# 02_SRAD_Avionics.net
KiCad netlist of a schematic drawn in Altium Designer
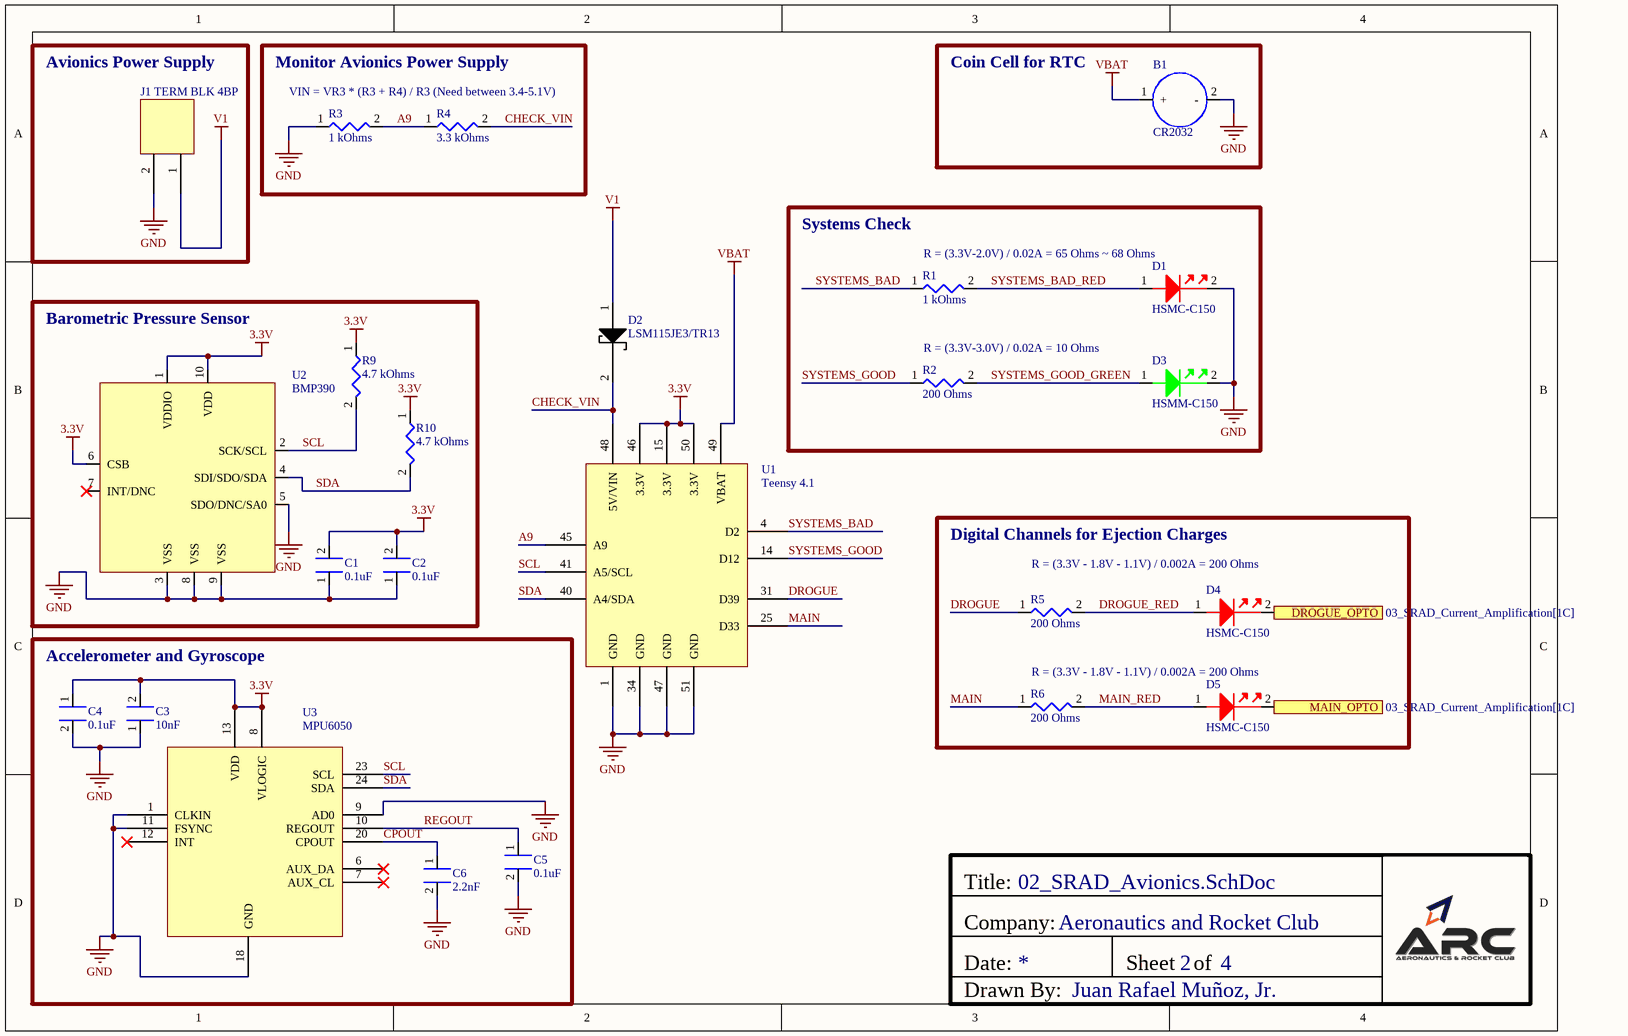
[diagram p0: 02_SRAD_Avionics.SchDoc]

(export (version "E")
  (design (tool "Eeschema 10.0.6"))
  (components
    (comp (ref "B1")
      (value "CR2032")
      (footprint "CR2032")
      (description "CR2032 Coin cell battery of 3V.")
      (libsource (lib "SRAD_SAC_Schlib") (part "CR2032"))
    )
    (comp (ref "C1")
      (value "0.1uF")
      (footprint "CAPC2012X14N_1_35mm_HEIGHT")
      (description "Capacitor Multilayer Ceramic MLCC - SMD/SMT 25 V 0.1uF X7R 0805 5%")
      (fields
        (field (name "MANUFACTURER") "Yageo")
        (field (name "MANUFACTURER PART NUMBER") "CC0805JPX7R8BB104")
      )
      (libsource (lib "SRAD_SAC_Schlib") (part "CC0805JPX7R8BB104"))
    )
    (comp (ref "C2")
      (value "0.1uF")
      (footprint "CAPC2012X14N_1_35mm_HEIGHT")
      (description "Capacitor Multilayer Ceramic MLCC - SMD/SMT 25 V 0.1uF X7R 0805 5%")
      (fields
        (field (name "MANUFACTURER") "Yageo")
        (field (name "MANUFACTURER PART NUMBER") "CC0805JPX7R8BB104")
      )
      (libsource (lib "SRAD_SAC_Schlib") (part "CC0805JPX7R8BB104"))
    )
    (comp (ref "C3")
      (value "10nF")
      (footprint "CAPC2012X07N_06mmHEIGHT")
      (description "Capacitor Multilayer Ceramic MLCC - SMD/SMT 50V 10nF X7R 0805 5%")
      (fields
        (field (name "MANUFACTURER") "Yageo")
        (field (name "MANUFACTURER PART NUMBER") "CC0805JRX7R9BB103")
      )
      (libsource (lib "SRAD_SAC_Schlib") (part "CC0805JRX7R9BB103"))
    )
    (comp (ref "C4")
      (value "0.1uF")
      (footprint "CAPC2012X14N_1_35mm_HEIGHT")
      (description "Capacitor Multilayer Ceramic MLCC - SMD/SMT 25 V 0.1uF X7R 0805 5%")
      (fields
        (field (name "MANUFACTURER") "Yageo")
        (field (name "MANUFACTURER PART NUMBER") "CC0805JPX7R8BB104")
      )
      (libsource (lib "SRAD_SAC_Schlib") (part "CC0805JPX7R8BB104"))
    )
    (comp (ref "C5")
      (value "0.1uF")
      (footprint "CAPC2012X14N_1_35mm_HEIGHT")
      (description "Capacitor Multilayer Ceramic MLCC - SMD/SMT 25 V 0.1uF X7R 0805 5%")
      (fields
        (field (name "MANUFACTURER") "Yageo")
        (field (name "MANUFACTURER PART NUMBER") "CC0805JPX7R8BB104")
      )
      (libsource (lib "SRAD_SAC_Schlib") (part "CC0805JPX7R8BB104"))
    )
    (comp (ref "C6")
      (value "2.2nF")
      (footprint "CAPC2012X07N_06mmHEIGHT")
      (description "Capacitor Multilayer Ceramic MLCC - SMD/SMT 50 V 2.2nF X7R 0805 5%")
      (fields
        (field (name "MANUFACTURER") "Yageo")
        (field (name "MANUFACTURER PART NUMBER") "CC0805JRX7R9BB222")
      )
      (libsource (lib "SRAD_SAC_Schlib") (part "CC0805JRX7R9BB222"))
    )
    (comp (ref "D1")
      (value "HSMC-C150")
      (footprint "DIOM3216X12N RED")
      (description "Red 626nm LED Indication - Discrete 1.9V 1206 (3216 Metric)")
      (fields (field (name "MANUFACTURER") "Broadcom Avago"))
      (libsource (lib "SRAD_SAC_Schlib") (part "DIOM3216X12N RED"))
    )
    (comp (ref "D2")
      (value "LSM115JE3/TR13")
      (footprint "DIOM4336X33N")
      (fields (field (name "MANUFACTURER") "Microchip"))
      (libsource (lib "SRAD_SAC_Schlib") (part "DIOM4336X33N Schottky Diode"))
    )
    (comp (ref "D3")
      (value "HSMM-C150")
      (footprint "DIOM3216X12N GREEN")
      (description "Green 525nm LED Indication - Discrete 3.3V 1206 (3216 Metric)")
      (fields (field (name "MANUFACTURER") "Broadcom Avago"))
      (libsource (lib "SRAD_SAC_Schlib") (part "DIOM3216X12N GREEN"))
    )
    (comp (ref "D4")
      (value "HSMC-C150")
      (footprint "DIOM3216X12N RED")
      (description "Red 626nm LED Indication - Discrete 1.9V 1206 (3216 Metric)")
      (fields (field (name "MANUFACTURER") "Broadcom Avago"))
      (libsource (lib "SRAD_SAC_Schlib") (part "DIOM3216X12N RED"))
    )
    (comp (ref "D5")
      (value "HSMC-C150")
      (footprint "DIOM3216X12N RED")
      (description "Red 626nm LED Indication - Discrete 1.9V 1206 (3216 Metric)")
      (fields (field (name "MANUFACTURER") "Broadcom Avago"))
      (libsource (lib "SRAD_SAC_Schlib") (part "DIOM3216X12N RED"))
    )
    (comp (ref "J1")
      (value "TERM BLK 4BP")
      (footprint "PCB TERM BLK 2P 2.54MM")
      (fields
        (field (name "MANUFACTURER") "TE Connectivity")
        (field (name "MANUFACTURER PART NUMBER") "282834-2")
        (field (name "VOLTAGE") "150V")
      )
      (libsource (lib "SRAD_SAC_Schlib") (part "PCB TERM BLK 2P 2.54MM"))
    )
    (comp (ref "R1")
      (value "1 kOhms")
      (footprint "RESC2012X06N")
      (description "1 kOhms ±1% 0.25W, 1/4W Chip Resistor 0805 (2012 Metric) Moisture Resistant Thick Film")
      (fields
        (field (name "MANUFACTURER") "Yageo")
        (field (name "MANUFACTURER PART NUMBER") "RC0805FR-7W1KL")
      )
      (libsource (lib "SRAD_SAC_Schlib") (part "RC0805FR-7W1KL Yageo"))
    )
    (comp (ref "R2")
      (value "200 Ohms")
      (footprint "RESC2012X06N")
      (description "200 Ohms ±1% 0.25W, 1/4W Chip Resistor 0805 (2012 Metric) Moisture Resistant Thick Film")
      (fields
        (field (name "MANUFACTURER") "Yageo")
        (field (name "MANUFACTURER PART NUMBER") "RC0805FR-7W200RL")
      )
      (libsource (lib "SRAD_SAC_Schlib") (part "RC0805FR-7W200RL Yageo"))
    )
    (comp (ref "R3")
      (value "1 kOhms")
      (footprint "RESC2012X06N")
      (description "1 kOhms ±1% 0.25W, 1/4W Chip Resistor 0805 (2012 Metric) Moisture Resistant Thick Film")
      (fields
        (field (name "MANUFACTURER") "Yageo")
        (field (name "MANUFACTURER PART NUMBER") "RC0805FR-7W1KL")
      )
      (libsource (lib "SRAD_SAC_Schlib") (part "RC0805FR-7W1KL Yageo"))
    )
    (comp (ref "R4")
      (value "3.3 kOhms")
      (footprint "RESC2012X06N")
      (description "3.3 kOhms ±1% 0.25W, 1/4W Chip Resistor 0805 (2012 Metric) Moisture Resistant Thick Film")
      (fields
        (field (name "MANUFACTURER") "Yageo")
        (field (name "MANUFACTURER PART NUMBER") "RC0805FR-7W3K3L")
      )
      (libsource (lib "SRAD_SAC_Schlib") (part "RC0805FR-7W3K3L Yageo"))
    )
    (comp (ref "R5")
      (value "200 Ohms")
      (footprint "RESC2012X06N")
      (description "200 Ohms ±1% 0.25W, 1/4W Chip Resistor 0805 (2012 Metric) Moisture Resistant Thick Film")
      (fields
        (field (name "MANUFACTURER") "Yageo")
        (field (name "MANUFACTURER PART NUMBER") "RC0805FR-7W200RL")
      )
      (libsource (lib "SRAD_SAC_Schlib") (part "RC0805FR-7W200RL Yageo"))
    )
    (comp (ref "R6")
      (value "200 Ohms")
      (footprint "RESC2012X06N")
      (description "200 Ohms ±1% 0.25W, 1/4W Chip Resistor 0805 (2012 Metric) Moisture Resistant Thick Film")
      (fields
        (field (name "MANUFACTURER") "Yageo")
        (field (name "MANUFACTURER PART NUMBER") "RC0805FR-7W200RL")
      )
      (libsource (lib "SRAD_SAC_Schlib") (part "RC0805FR-7W200RL Yageo"))
    )
    (comp (ref "R9")
      (value "4.7 kOhms")
      (footprint "RESC2012X06N")
      (description "4.7 kOhms ±1% 0.25W, 1/4W Chip Resistor 0805 (2012 Metric) Moisture Resistant Thick Film")
      (fields
        (field (name "MANUFACTURER") "Yageo")
        (field (name "MANUFACTURER PART NUMBER") "RC0805FR-7W4K7L")
      )
      (libsource (lib "SRAD_SAC_Schlib") (part "RC0805FR-7W4K7L Yageo"))
    )
    (comp (ref "R10")
      (value "4.7 kOhms")
      (footprint "RESC2012X06N")
      (description "4.7 kOhms ±1% 0.25W, 1/4W Chip Resistor 0805 (2012 Metric) Moisture Resistant Thick Film")
      (fields
        (field (name "MANUFACTURER") "Yageo")
        (field (name "MANUFACTURER PART NUMBER") "RC0805FR-7W4K7L")
      )
      (libsource (lib "SRAD_SAC_Schlib") (part "RC0805FR-7W4K7L Yageo"))
    )
    (comp (ref "U1")
      (value "Teensy 4.1")
      (footprint "Teensy 4.1")
      (fields (field (name "MANUFACTURER") "SparkFun") (field (name "MANUFACTURER PART NUMBER") "DEV-16996"))
      (libsource (lib "SRAD_SAC_Schlib") (part "Teensy 4.1"))
    )
    (comp (ref "U2")
      (value "BMP390")
      (footprint "BMP390")
      (description "Barometric pressure sensor manufactured by Bosch.")
      (libsource (lib "SRAD_SAC_Schlib") (part "BMP390"))
    )
    (comp (ref "U3")
      (value "MPU6050")
      (footprint "MPU6050")
      (libsource (lib "SRAD_SAC_Schlib") (part "MPU6050"))
    )
  )
  (nets
    (net (code "1") (name "/A9") (class "Default")
      (node (ref "R3") (pin "2") (pinfunction "2_2") (pintype "passive"))
      (node (ref "R4") (pin "1") (pinfunction "1_1") (pintype "passive"))
      (node (ref "U1") (pin "45") (pinfunction "A9_45") (pintype "passive"))
    )
    (net (code "2") (name "/CHECK_VIN") (class "Default")
      (node (ref "D2") (pin "2") (pinfunction "-_2") (pintype "passive"))
      (node (ref "R4") (pin "2") (pinfunction "2_2") (pintype "passive"))
      (node (ref "U1") (pin "48") (pinfunction "5V/VIN_48") (pintype "passive"))
    )
    (net (code "3") (name "/CPOUT") (class "Default")
      (node (ref "C6") (pin "1") (pinfunction "1_1") (pintype "passive"))
      (node (ref "U3") (pin "20") (pinfunction "CPOUT_20") (pintype "passive"))
    )
    (net (code "4") (name "/DROGUE") (class "Default")
      (node (ref "R5") (pin "1") (pinfunction "1_1") (pintype "passive"))
      (node (ref "U1") (pin "31") (pinfunction "D39_31") (pintype "passive"))
    )
    (net (code "5") (name "/DROGUE_OPTO") (class "Default")
      (node (ref "D4") (pin "2") (pinfunction "-_2") (pintype "passive"))
    )
    (net (code "6") (name "/DROGUE_RED") (class "Default")
      (node (ref "D4") (pin "1") (pinfunction "+_1") (pintype "passive"))
      (node (ref "R5") (pin "2") (pinfunction "2_2") (pintype "passive"))
    )
    (net (code "7") (name "/MAIN") (class "Default")
      (node (ref "R6") (pin "1") (pinfunction "1_1") (pintype "passive"))
      (node (ref "U1") (pin "25") (pinfunction "D33_25") (pintype "passive"))
    )
    (net (code "8") (name "/MAIN_OPTO") (class "Default")
      (node (ref "D5") (pin "2") (pinfunction "-_2") (pintype "passive"))
    )
    (net (code "9") (name "/MAIN_RED") (class "Default")
      (node (ref "D5") (pin "1") (pinfunction "+_1") (pintype "passive"))
      (node (ref "R6") (pin "2") (pinfunction "2_2") (pintype "passive"))
    )
    (net (code "10") (name "/REGOUT") (class "Default")
      (node (ref "C5") (pin "1") (pinfunction "1_1") (pintype "passive"))
      (node (ref "U3") (pin "10") (pinfunction "REGOUT_10") (pintype "passive"))
    )
    (net (code "11") (name "/SCL") (class "Default")
      (node (ref "R9") (pin "2") (pinfunction "2_2") (pintype "passive"))
      (node (ref "U1") (pin "41") (pinfunction "A5/SCL_41") (pintype "passive"))
      (node (ref "U2") (pin "2") (pinfunction "SCK/SCL_2") (pintype "passive"))
      (node (ref "U3") (pin "23") (pinfunction "SCL_23") (pintype "passive"))
    )
    (net (code "12") (name "/SDA") (class "Default")
      (node (ref "R10") (pin "2") (pinfunction "2_2") (pintype "passive"))
      (node (ref "U1") (pin "40") (pinfunction "A4/SDA_40") (pintype "passive"))
      (node (ref "U2") (pin "4") (pinfunction "SDI/SDO/SDA_4") (pintype "passive"))
      (node (ref "U3") (pin "24") (pinfunction "SDA_24") (pintype "passive"))
    )
    (net (code "13") (name "/SYSTEMS_BAD") (class "Default")
      (node (ref "R1") (pin "1") (pinfunction "1_1") (pintype "passive"))
      (node (ref "U1") (pin "4") (pinfunction "D2_4") (pintype "passive"))
    )
    (net (code "14") (name "/SYSTEMS_BAD_RED") (class "Default")
      (node (ref "D1") (pin "1") (pinfunction "+_1") (pintype "passive"))
      (node (ref "R1") (pin "2") (pinfunction "2_2") (pintype "passive"))
    )
    (net (code "15") (name "/SYSTEMS_GOOD") (class "Default")
      (node (ref "R2") (pin "1") (pinfunction "1_1") (pintype "passive"))
      (node (ref "U1") (pin "14") (pinfunction "D12_14") (pintype "passive"))
    )
    (net (code "16") (name "/SYSTEMS_GOOD_GREEN") (class "Default")
      (node (ref "D3") (pin "1") (pinfunction "+_1") (pintype "passive"))
      (node (ref "R2") (pin "2") (pinfunction "2_2") (pintype "passive"))
    )
    (net (code "17") (name "3.3V") (class "Default")
      (node (ref "C1") (pin "2") (pinfunction "2_2") (pintype "passive"))
      (node (ref "C2") (pin "2") (pinfunction "2_2") (pintype "passive"))
      (node (ref "C3") (pin "2") (pinfunction "2_2") (pintype "passive"))
      (node (ref "C4") (pin "1") (pinfunction "1_1") (pintype "passive"))
      (node (ref "R10") (pin "1") (pinfunction "1_1") (pintype "passive"))
      (node (ref "R9") (pin "1") (pinfunction "1_1") (pintype "passive"))
      (node (ref "U1") (pin "15") (pinfunction "3.3V_15") (pintype "passive"))
      (node (ref "U1") (pin "46") (pinfunction "3.3V_46") (pintype "passive"))
      (node (ref "U1") (pin "50") (pinfunction "3.3V_50") (pintype "passive"))
      (node (ref "U2") (pin "1") (pinfunction "VDDIO_1") (pintype "passive"))
      (node (ref "U2") (pin "10") (pinfunction "VDD_10") (pintype "passive"))
      (node (ref "U2") (pin "6") (pinfunction "CSB_6") (pintype "passive"))
      (node (ref "U3") (pin "13") (pinfunction "VDD_13") (pintype "passive"))
      (node (ref "U3") (pin "8") (pinfunction "VLOGIC_8") (pintype "passive"))
    )
    (net (code "18") (name "GND") (class "Default")
      (node (ref "B1") (pin "2") (pinfunction "-_2") (pintype "passive"))
      (node (ref "C1") (pin "1") (pinfunction "1_1") (pintype "passive"))
      (node (ref "C2") (pin "1") (pinfunction "1_1") (pintype "passive"))
      (node (ref "C3") (pin "1") (pinfunction "1_1") (pintype "passive"))
      (node (ref "C4") (pin "2") (pinfunction "2_2") (pintype "passive"))
      (node (ref "C5") (pin "2") (pinfunction "2_2") (pintype "passive"))
      (node (ref "C6") (pin "2") (pinfunction "2_2") (pintype "passive"))
      (node (ref "D1") (pin "2") (pinfunction "-_2") (pintype "passive"))
      (node (ref "D3") (pin "2") (pinfunction "-_2") (pintype "passive"))
      (node (ref "J1") (pin "2") (pinfunction "-_2") (pintype "passive"))
      (node (ref "R3") (pin "1") (pinfunction "1_1") (pintype "passive"))
      (node (ref "U1") (pin "1") (pinfunction "GND_1") (pintype "passive"))
      (node (ref "U1") (pin "34") (pinfunction "GND_34") (pintype "passive"))
      (node (ref "U1") (pin "47") (pinfunction "GND_47") (pintype "passive"))
      (node (ref "U1") (pin "51") (pinfunction "GND_51") (pintype "passive"))
      (node (ref "U2") (pin "3") (pinfunction "VSS_3") (pintype "passive"))
      (node (ref "U2") (pin "5") (pinfunction "SDO/DNC/SA0_5") (pintype "passive"))
      (node (ref "U2") (pin "8") (pinfunction "VSS_8") (pintype "passive"))
      (node (ref "U2") (pin "9") (pinfunction "VSS_9") (pintype "passive"))
      (node (ref "U3") (pin "1") (pinfunction "CLKIN_1") (pintype "passive"))
      (node (ref "U3") (pin "11") (pinfunction "FSYNC_11") (pintype "passive"))
      (node (ref "U3") (pin "18") (pinfunction "GND_18") (pintype "passive"))
      (node (ref "U3") (pin "9") (pinfunction "AD0_9") (pintype "passive"))
    )
    (net (code "19") (name "V1") (class "Default")
      (node (ref "D2") (pin "1") (pinfunction "+_1") (pintype "passive"))
      (node (ref "J1") (pin "1") (pinfunction "+_1") (pintype "passive"))
    )
    (net (code "20") (name "VBAT") (class "Default")
      (node (ref "B1") (pin "1") (pinfunction "+_1") (pintype "passive"))
      (node (ref "U1") (pin "49") (pinfunction "VBAT_49") (pintype "passive"))
    )
    (net (code "21") (name "unconnected-(U2-INT{slash}DNC-Pad7)") (class "Default")
      (node (ref "U2") (pin "7") (pinfunction "INT/DNC_7") (pintype "passive+no_connect"))
    )
    (net (code "22") (name "unconnected-(U3-AUX_CL-Pad7)") (class "Default")
      (node (ref "U3") (pin "7") (pinfunction "AUX_CL_7") (pintype "passive+no_connect"))
    )
    (net (code "23") (name "unconnected-(U3-AUX_DA-Pad6)") (class "Default")
      (node (ref "U3") (pin "6") (pinfunction "AUX_DA_6") (pintype "passive+no_connect"))
    )
    (net (code "24") (name "unconnected-(U3-INT-Pad12)") (class "Default")
      (node (ref "U3") (pin "12") (pinfunction "INT_12") (pintype "passive+no_connect"))
    )
  )
)
